# current_stub.net
KiCad netlist of a schematic drawn in EAGLE
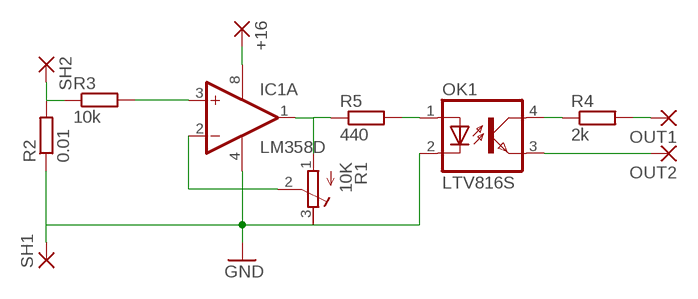
[diagram p0: schematic, sheet 1]

(export (version "E")
  (design (tool "Eeschema 10.0.6"))
  (components
    (comp (ref "+16")
      (value "SMD2")
      (footprint "eagle-import:SMD1,27-2,54")
      (libsource (lib "eagle-import") (part "SMD2"))
    )
    (comp (ref "IC1")
      (value "LM358D")
      (footprint "eagle-import:SO08")
      (libsource (lib "eagle-import") (part "LM358D"))
    )
    (comp (ref "OK1")
      (value "LTV816S")
      (footprint "eagle-import:SMD4")
      (libsource (lib "eagle-import") (part "LTV816S"))
    )
    (comp (ref "OUT1")
      (value "SMD2")
      (footprint "eagle-import:SMD1,27-2,54")
      (libsource (lib "eagle-import") (part "SMD2"))
    )
    (comp (ref "OUT2")
      (value "SMD2")
      (footprint "eagle-import:SMD1,27-2,54")
      (libsource (lib "eagle-import") (part "SMD2"))
    )
    (comp (ref "R1")
      (value "10K")
      (footprint "eagle-import:RTRIM3296W")
      (libsource (lib "eagle-import") (part "R-TRIMM3296W"))
    )
    (comp (ref "R2")
      (value "0.01")
      (footprint "eagle-import:R2512")
      (libsource (lib "eagle-import") (part "R-EU_R2512"))
    )
    (comp (ref "R3")
      (value "10k")
      (footprint "eagle-import:M0805")
      (libsource (lib "eagle-import") (part "R-EU_M0805"))
    )
    (comp (ref "R4")
      (value "2k")
      (footprint "eagle-import:M0805")
      (libsource (lib "eagle-import") (part "R-EU_M0805"))
    )
    (comp (ref "R5")
      (value "440")
      (footprint "eagle-import:M0805")
      (libsource (lib "eagle-import") (part "R-EU_M0805"))
    )
    (comp (ref "SH1")
      (value "SMD2")
      (footprint "eagle-import:SMD1,27-2,54")
      (libsource (lib "eagle-import") (part "SMD2"))
    )
    (comp (ref "SH2")
      (value "SMD2")
      (footprint "eagle-import:SMD1,27-2,54")
      (libsource (lib "eagle-import") (part "SMD2"))
    )
  )
  (nets
    (net (code "1") (name "GND") (class "Default")
      (node (ref "IC1") (pin "4") (pinfunction "V-_4") (pintype "power_in"))
      (node (ref "OK1") (pin "2") (pinfunction "C_2") (pintype "passive"))
      (node (ref "R1") (pin "3") (pinfunction "E_3") (pintype "passive"))
      (node (ref "R2") (pin "1") (pinfunction "1_1") (pintype "passive"))
      (node (ref "SH1") (pin "1") (pinfunction "P_1") (pintype "passive"))
    )
    (net (code "2") (name "Net-(+16-P)") (class "Default")
      (node (ref "+16") (pin "1") (pinfunction "P_1") (pintype "passive"))
      (node (ref "IC1") (pin "8") (pinfunction "V+_8") (pintype "power_in"))
    )
    (net (code "3") (name "Net-(IC1A-+IN)") (class "Default")
      (node (ref "IC1") (pin "3") (pinfunction "+IN_3") (pintype "input"))
      (node (ref "R3") (pin "2") (pinfunction "2_2") (pintype "passive"))
    )
    (net (code "4") (name "Net-(IC1A--IN)") (class "Default")
      (node (ref "IC1") (pin "2") (pinfunction "-IN_2") (pintype "input"))
      (node (ref "R1") (pin "2") (pinfunction "S_2") (pintype "passive"))
    )
    (net (code "5") (name "Net-(IC1A-OUT)") (class "Default")
      (node (ref "IC1") (pin "1") (pinfunction "OUT_1") (pintype "output"))
      (node (ref "R1") (pin "1") (pinfunction "A_1") (pintype "passive"))
      (node (ref "R5") (pin "1") (pinfunction "1_1") (pintype "passive"))
    )
    (net (code "6") (name "Net-(OK1-A)") (class "Default")
      (node (ref "OK1") (pin "1") (pinfunction "A_1") (pintype "passive"))
      (node (ref "R5") (pin "2") (pinfunction "2_2") (pintype "passive"))
    )
    (net (code "7") (name "Net-(OK1-COL)") (class "Default")
      (node (ref "OK1") (pin "4") (pinfunction "COL_4") (pintype "passive"))
      (node (ref "R4") (pin "1") (pinfunction "1_1") (pintype "passive"))
    )
    (net (code "8") (name "Net-(OK1-EMIT)") (class "Default")
      (node (ref "OK1") (pin "3") (pinfunction "EMIT_3") (pintype "passive"))
      (node (ref "OUT2") (pin "1") (pinfunction "P_1") (pintype "passive"))
    )
    (net (code "9") (name "Net-(OUT1-P)") (class "Default")
      (node (ref "OUT1") (pin "1") (pinfunction "P_1") (pintype "passive"))
      (node (ref "R4") (pin "2") (pinfunction "2_2") (pintype "passive"))
    )
    (net (code "10") (name "Net-(SH2-P)") (class "Default")
      (node (ref "R2") (pin "2") (pinfunction "2_2") (pintype "passive"))
      (node (ref "R3") (pin "1") (pinfunction "1_1") (pintype "passive"))
      (node (ref "SH2") (pin "1") (pinfunction "P_1") (pintype "passive"))
    )
  )
)
